# DC_Step-Down_Converter.net
KiCad netlist of a schematic drawn in Altium Designer
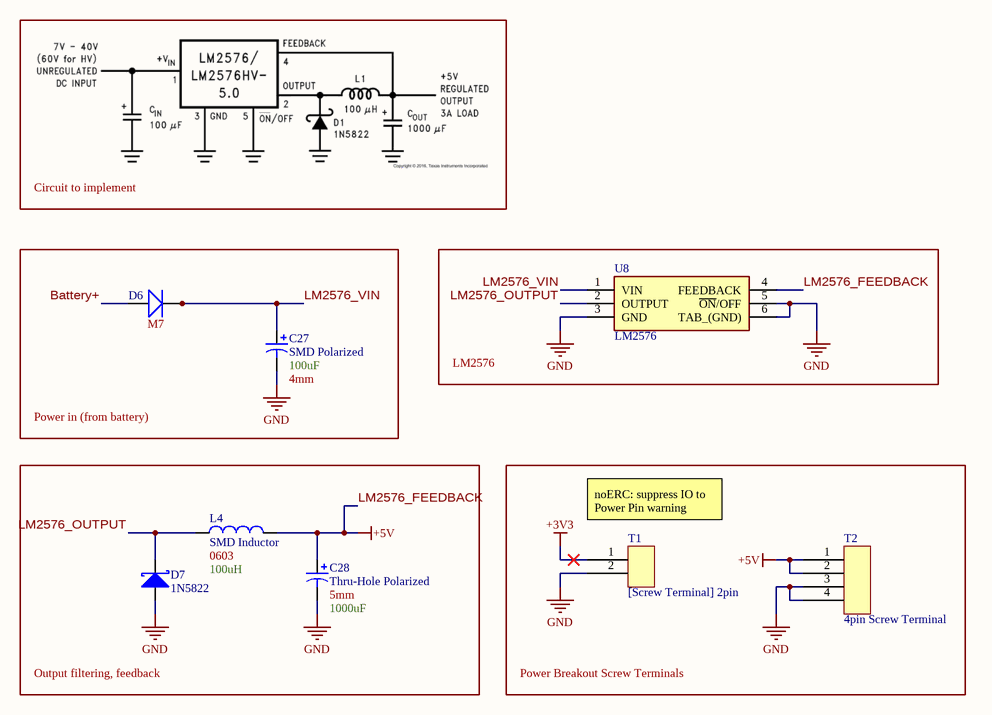
[diagram p0: DC Step-Down Converter.SchDoc]

(export (version "E")
  (design (tool "Eeschema 10.0.6"))
  (components
    (comp (ref "C27")
      (value "SMD Polarized")
      (footprint "[Cap] SMD Polarized, 4mm")
      (fields (field (name "CAPACITANCE") "100uF") (field (name "DIAMETER") "4mm"))
      (libsource (lib "RADM Components") (part "[Cap] SMD Polarized"))
    )
    (comp (ref "C28")
      (value "Thru-Hole Polarized")
      (footprint "[Cap] Thru-Hole Polarized 5mm")
      (fields (field (name "PIN SPACING") "5mm") (field (name "CAPACITANCE") "1000uF"))
      (libsource (lib "RADM Components") (part "[Cap] Thru-Hole Polarized"))
    )
    (comp (ref "D6")
      (value "Rectifier")
      (footprint "[Diode] SMD M7")
      (description "Generic")
      (fields (field (name "SIZE PACKAGE") "M7"))
      (libsource (lib "RADM Components") (part "[Diode] SMD Rectifier"))
    )
    (comp (ref "D7")
      (value "1N5822")
      (footprint "[Diode] Thru-Hole Schottky")
      (fields (field (name "MOUSER PART #") "511-1N5822"))
      (libsource (lib "RADM Components") (part "[Diode] Thru-Hole Schottky"))
    )
    (comp (ref "L4")
      (value "SMD Inductor")
      (footprint "[Inductor] SMD 0603")
      (fields (field (name "SIZE PACKAGE") "0603") (field (name "INDUCTANCE") "100uH"))
      (libsource (lib "RADM Components") (part "[Inductor] SMD Inductor"))
    )
    (comp (ref "T1")
      (value "[Screw Terminal] 2pin")
      (footprint "[Screw Terminal] 2pin")
      (libsource (lib "RADM Components") (part "[Screw Terminal] 2pin"))
    )
    (comp (ref "T2")
      (value "4pin Screw Terminal")
      (footprint "[Screw Terminal] 4pin")
      (libsource (lib "RADM Components") (part "[Screw Terminal] 4pin"))
    )
    (comp (ref "U8")
      (value "LM2576")
      (footprint "[IC] Buck Converter")
      (libsource (lib "RADM Components") (part "[IC] Buck Converter"))
    )
  )
  (nets
    (net (code "1") (name "+3V3") (class "Default") (node (ref "T1") (pin "1") (pintype "power_in")))
    (net (code "2") (name "+5V") (class "Default")
      (node (ref "C28") (pin "1") (pinfunction "1_1") (pintype "passive"))
      (node (ref "L4") (pin "2") (pinfunction "2_2") (pintype "passive"))
      (node (ref "T2") (pin "1") (pintype "power_in"))
      (node (ref "T2") (pin "2") (pintype "power_in"))
      (node (ref "U8") (pin "4") (pinfunction "FEEDBACK_4") (pintype "power_in"))
    )
    (net (code "3") (name "/Battery+") (class "Default")
      (node (ref "D6") (pin "2") (pinfunction "Anode_2") (pintype "power_in"))
    )
    (net (code "4") (name "/LM2576_OUTPUT") (class "Default")
      (node (ref "D7") (pin "1") (pinfunction "K_1") (pintype "passive"))
      (node (ref "L4") (pin "1") (pinfunction "1_1") (pintype "passive"))
      (node (ref "U8") (pin "2") (pinfunction "OUTPUT_2") (pintype "power_in"))
    )
    (net (code "5") (name "/LM2576_VIN") (class "Default")
      (node (ref "C27") (pin "1") (pinfunction "1_1") (pintype "passive"))
      (node (ref "D6") (pin "1") (pinfunction "Cathode_1") (pintype "power_in"))
      (node (ref "U8") (pin "1") (pinfunction "VIN_1") (pintype "power_in"))
    )
    (net (code "6") (name "GND") (class "Default")
      (node (ref "C27") (pin "2") (pinfunction "2_2") (pintype "passive"))
      (node (ref "C28") (pin "2") (pinfunction "2_2") (pintype "passive"))
      (node (ref "D7") (pin "2") (pinfunction "A_2") (pintype "passive"))
      (node (ref "T1") (pin "2") (pintype "power_in"))
      (node (ref "T2") (pin "3") (pintype "power_in"))
      (node (ref "T2") (pin "4") (pintype "power_in"))
      (node (ref "U8") (pin "3") (pinfunction "GND_3") (pintype "power_in"))
      (node (ref "U8") (pin "5") (pinfunction "~{ON}/OFF_5") (pintype "power_in"))
      (node (ref "U8") (pin "6") (pinfunction "TAB_(GND)_6") (pintype "power_in"))
    )
  )
)
